# working.net
KiCad netlist of a schematic drawn in EAGLE
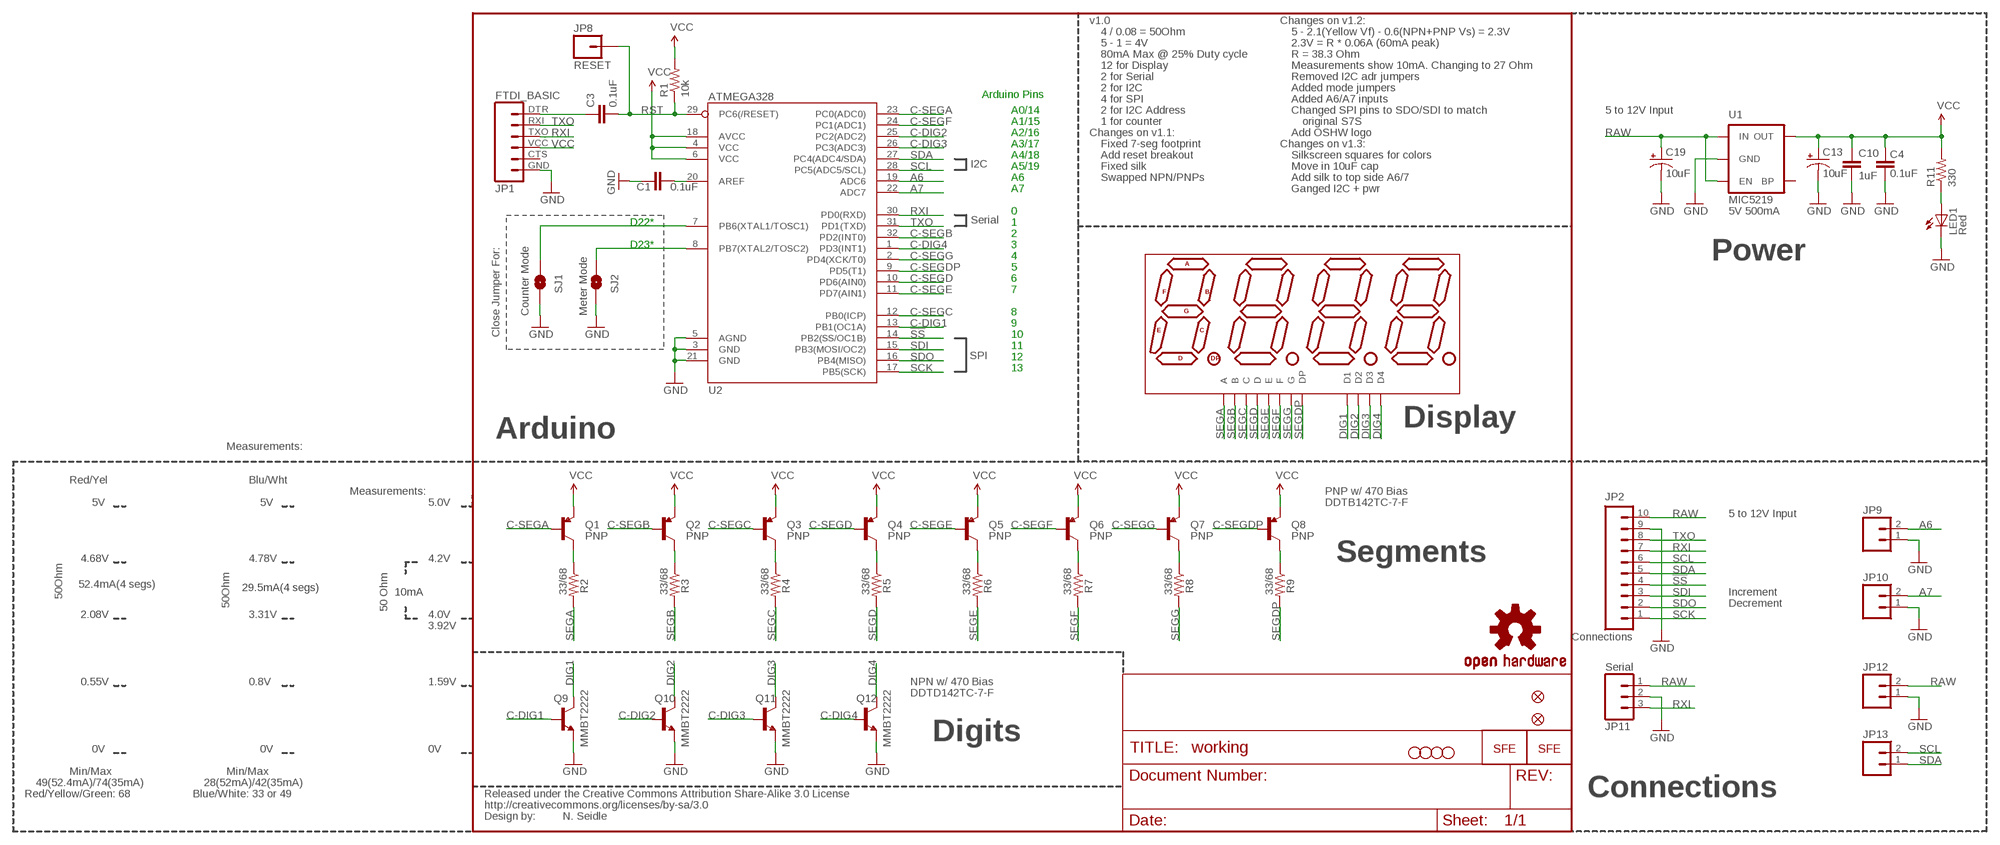
[diagram p0: schematic, sheet 1]

(export (version "E")
  (design (tool "Eeschema 10.0.6"))
  (components
    (comp (ref "C1")
      (value "0.1uF")
      (footprint "eagle-import:0402-CAP")
      (libsource (lib "eagle-import") (part "CAP0402-CAP"))
    )
    (comp (ref "C3")
      (value "0.1uF")
      (footprint "eagle-import:0402-CAP")
      (libsource (lib "eagle-import") (part "CAP0402-CAP"))
    )
    (comp (ref "C4")
      (value "0.1uF")
      (footprint "eagle-import:0402-CAP")
      (libsource (lib "eagle-import") (part "CAP0402-CAP"))
    )
    (comp (ref "C10")
      (value "1uF")
      (footprint "eagle-import:0402-CAP")
      (libsource (lib "eagle-import") (part "CAP0402-CAP"))
    )
    (comp (ref "C13")
      (value "10uF")
      (footprint "eagle-import:EIA3216")
      (libsource (lib "eagle-import") (part "CAP_POL1206"))
    )
    (comp (ref "C19")
      (value "10uF")
      (footprint "eagle-import:EIA3216")
      (libsource (lib "eagle-import") (part "CAP_POL1206"))
    )
    (comp (ref "JP1")
      (value "FTDI_BASIC")
      (footprint "eagle-import:FTDI_BASIC")
      (libsource (lib "eagle-import") (part "FTDI_BASICPTH"))
    )
    (comp (ref "JP2")
      (value "Connections")
      (footprint "eagle-import:1X10")
      (libsource (lib "eagle-import") (part "M10{dblquote}"))
    )
    (comp (ref "JP3")
      (value "STAND-OFF")
      (footprint "eagle-import:STAND-OFF")
      (libsource (lib "eagle-import") (part "STAND-OFF"))
    )
    (comp (ref "JP4")
      (value "STAND-OFF")
      (footprint "eagle-import:STAND-OFF")
      (libsource (lib "eagle-import") (part "STAND-OFF"))
    )
    (comp (ref "JP5")
      (value "STAND-OFF")
      (footprint "eagle-import:STAND-OFF")
      (libsource (lib "eagle-import") (part "STAND-OFF"))
    )
    (comp (ref "JP6")
      (value "STAND-OFF")
      (footprint "eagle-import:STAND-OFF")
      (libsource (lib "eagle-import") (part "STAND-OFF"))
    )
    (comp (ref "JP7")
      (value "FIDUCIALUFIDUCIAL")
      (footprint "eagle-import:MICRO-FIDUCIAL")
      (libsource (lib "eagle-import") (part "FIDUCIALUFIDUCIAL"))
    )
    (comp (ref "JP8")
      (value "RESET")
      (footprint "eagle-import:1X01")
      (libsource (lib "eagle-import") (part "M01PTH"))
    )
    (comp (ref "JP9")
      (value "M02PTH")
      (footprint "eagle-import:1X02")
      (libsource (lib "eagle-import") (part "M02PTH"))
    )
    (comp (ref "JP10")
      (value "M02PTH")
      (footprint "eagle-import:1X02")
      (libsource (lib "eagle-import") (part "M02PTH"))
    )
    (comp (ref "JP11")
      (value "Serial")
      (footprint "eagle-import:JST-3-PTH")
      (libsource (lib "eagle-import") (part "M03JST-PTH"))
    )
    (comp (ref "JP12")
      (value "M02PTH")
      (footprint "eagle-import:1X02")
      (libsource (lib "eagle-import") (part "M02PTH"))
    )
    (comp (ref "JP13")
      (value "M02PTH")
      (footprint "eagle-import:1X02")
      (libsource (lib "eagle-import") (part "M02PTH"))
    )
    (comp (ref "JP14")
      (value "FIDUCIALUFIDUCIAL")
      (footprint "eagle-import:MICRO-FIDUCIAL")
      (libsource (lib "eagle-import") (part "FIDUCIALUFIDUCIAL"))
    )
    (comp (ref "LED1")
      (value "Red")
      (footprint "eagle-import:LED-0603")
      (libsource (lib "eagle-import") (part "LED0603"))
    )
    (comp (ref "Q1")
      (value "PNP")
      (footprint "eagle-import:SOT23-3")
      (libsource (lib "eagle-import") (part "TRANSISTOR_PNPSMD"))
    )
    (comp (ref "Q2")
      (value "PNP")
      (footprint "eagle-import:SOT23-3")
      (libsource (lib "eagle-import") (part "TRANSISTOR_PNPSMD"))
    )
    (comp (ref "Q3")
      (value "PNP")
      (footprint "eagle-import:SOT23-3")
      (libsource (lib "eagle-import") (part "TRANSISTOR_PNPSMD"))
    )
    (comp (ref "Q4")
      (value "PNP")
      (footprint "eagle-import:SOT23-3")
      (libsource (lib "eagle-import") (part "TRANSISTOR_PNPSMD"))
    )
    (comp (ref "Q5")
      (value "PNP")
      (footprint "eagle-import:SOT23-3")
      (libsource (lib "eagle-import") (part "TRANSISTOR_PNPSMD"))
    )
    (comp (ref "Q6")
      (value "PNP")
      (footprint "eagle-import:SOT23-3")
      (libsource (lib "eagle-import") (part "TRANSISTOR_PNPSMD"))
    )
    (comp (ref "Q7")
      (value "PNP")
      (footprint "eagle-import:SOT23-3")
      (libsource (lib "eagle-import") (part "TRANSISTOR_PNPSMD"))
    )
    (comp (ref "Q8")
      (value "PNP")
      (footprint "eagle-import:SOT23-3")
      (libsource (lib "eagle-import") (part "TRANSISTOR_PNPSMD"))
    )
    (comp (ref "Q9")
      (value "MMBT2222")
      (footprint "eagle-import:SOT23-3")
      (libsource (lib "eagle-import") (part "TRANSISTOR_NPNSOT23-3"))
    )
    (comp (ref "Q10")
      (value "MMBT2222")
      (footprint "eagle-import:SOT23-3")
      (libsource (lib "eagle-import") (part "TRANSISTOR_NPNSOT23-3"))
    )
    (comp (ref "Q11")
      (value "MMBT2222")
      (footprint "eagle-import:SOT23-3")
      (libsource (lib "eagle-import") (part "TRANSISTOR_NPNSOT23-3"))
    )
    (comp (ref "Q12")
      (value "MMBT2222")
      (footprint "eagle-import:SOT23-3")
      (libsource (lib "eagle-import") (part "TRANSISTOR_NPNSOT23-3"))
    )
    (comp (ref "R1")
      (value "10k")
      (footprint "eagle-import:0402-RES")
      (libsource (lib "eagle-import") (part "RESISTOR0402-RES"))
    )
    (comp (ref "R2")
      (value "33/68")
      (footprint "eagle-import:0402-RES")
      (libsource (lib "eagle-import") (part "RESISTOR0402-RES"))
    )
    (comp (ref "R3")
      (value "33/68")
      (footprint "eagle-import:0402-RES")
      (libsource (lib "eagle-import") (part "RESISTOR0402-RES"))
    )
    (comp (ref "R4")
      (value "33/68")
      (footprint "eagle-import:0402-RES")
      (libsource (lib "eagle-import") (part "RESISTOR0402-RES"))
    )
    (comp (ref "R5")
      (value "33/68")
      (footprint "eagle-import:0402-RES")
      (libsource (lib "eagle-import") (part "RESISTOR0402-RES"))
    )
    (comp (ref "R6")
      (value "33/68")
      (footprint "eagle-import:0402-RES")
      (libsource (lib "eagle-import") (part "RESISTOR0402-RES"))
    )
    (comp (ref "R7")
      (value "33/68")
      (footprint "eagle-import:0402-RES")
      (libsource (lib "eagle-import") (part "RESISTOR0402-RES"))
    )
    (comp (ref "R8")
      (value "33/68")
      (footprint "eagle-import:0402-RES")
      (libsource (lib "eagle-import") (part "RESISTOR0402-RES"))
    )
    (comp (ref "R9")
      (value "33/68")
      (footprint "eagle-import:0402-RES")
      (libsource (lib "eagle-import") (part "RESISTOR0402-RES"))
    )
    (comp (ref "R11")
      (value "330")
      (footprint "eagle-import:0402-RES")
      (libsource (lib "eagle-import") (part "RESISTOR0402-RES"))
    )
    (comp (ref "SJ1")
      (value "Counter Ctl")
      (footprint "eagle-import:SJ_2S-NO")
      (libsource (lib "eagle-import") (part "SOLDERJUMPERNO"))
    )
    (comp (ref "SJ2")
      (value "Counter Ctl")
      (footprint "eagle-import:SJ_2S-NO")
      (libsource (lib "eagle-import") (part "SOLDERJUMPERNO"))
    )
    (comp (ref "U$2")
      (value "LOGO-SFESK")
      (footprint "eagle-import:SFE-LOGO-FLAME")
      (libsource (lib "eagle-import") (part "LOGO-SFESK"))
    )
    (comp (ref "U$3")
      (value "CREATIVE_COMMONS")
      (footprint "eagle-import:CREATIVE_COMMONS")
      (libsource (lib "eagle-import") (part "CREATIVE_COMMONS"))
    )
    (comp (ref "U$4")
      (value "OSHW-LOGOS")
      (footprint "eagle-import:OSHW-LOGO-S")
      (libsource (lib "eagle-import") (part "OSHW-LOGOS"))
    )
    (comp (ref "U$7")
      (value "LOGO-SFENW2")
      (footprint "eagle-import:SFE-NEW-WEB")
      (libsource (lib "eagle-import") (part "LOGO-SFENW2"))
    )
    (comp (ref "U1")
      (value "MIC5219")
      (footprint "eagle-import:SOT23-5")
      (libsource (lib "eagle-import") (part "V_REG_LDOSMD"))
    )
    (comp (ref "U2")
      (value "ATMEGA328")
      (footprint "eagle-import:TQFP32-08")
      (libsource (lib "eagle-import") (part "ATMEGA168"))
    )
    (comp (ref "U3")
      (value "7-SEGMENT-4DIGIT-COUNTERPTH")
      (footprint "eagle-import:7-SEGMENT-4DIGIT-COUNTER")
      (libsource (lib "eagle-import") (part "7-SEGMENT-4DIGIT-COUNTERPTH"))
    )
  )
  (nets
    (net (code "1") (name "/A6") (class "Default")
      (node (ref "JP9") (pin "2") (pinfunction "2_2") (pintype "passive"))
      (node (ref "U2") (pin "19") (pinfunction "ADC6_19") (pintype "bidirectional"))
    )
    (net (code "2") (name "/A7") (class "Default")
      (node (ref "JP10") (pin "2") (pinfunction "2_2") (pintype "passive"))
      (node (ref "U2") (pin "22") (pinfunction "ADC7_22") (pintype "bidirectional"))
    )
    (net (code "3") (name "/C-DIG1") (class "Default")
      (node (ref "Q9") (pin "1") (pinfunction "B_1") (pintype "passive"))
      (node (ref "U2") (pin "13") (pinfunction "PB1(OC1A)_13") (pintype "bidirectional"))
    )
    (net (code "4") (name "/C-DIG2") (class "Default")
      (node (ref "Q10") (pin "1") (pinfunction "B_1") (pintype "passive"))
      (node (ref "U2") (pin "25") (pinfunction "PC2(ADC2)_25") (pintype "bidirectional"))
    )
    (net (code "5") (name "/C-DIG3") (class "Default")
      (node (ref "Q11") (pin "1") (pinfunction "B_1") (pintype "passive"))
      (node (ref "U2") (pin "26") (pinfunction "PC3(ADC3)_26") (pintype "bidirectional"))
    )
    (net (code "6") (name "/C-DIG4") (class "Default")
      (node (ref "Q12") (pin "1") (pinfunction "B_1") (pintype "passive"))
      (node (ref "U2") (pin "1") (pinfunction "PD3(INT1)_1") (pintype "bidirectional"))
    )
    (net (code "7") (name "/C-SEGA") (class "Default")
      (node (ref "Q1") (pin "1") (pinfunction "B_1") (pintype "passive"))
      (node (ref "U2") (pin "23") (pinfunction "PC0(ADC0)_23") (pintype "bidirectional"))
    )
    (net (code "8") (name "/C-SEGB") (class "Default")
      (node (ref "Q2") (pin "1") (pinfunction "B_1") (pintype "passive"))
      (node (ref "U2") (pin "32") (pinfunction "PD2(INT0)_32") (pintype "bidirectional"))
    )
    (net (code "9") (name "/C-SEGC") (class "Default")
      (node (ref "Q3") (pin "1") (pinfunction "B_1") (pintype "passive"))
      (node (ref "U2") (pin "12") (pinfunction "PB0(ICP)_12") (pintype "bidirectional"))
    )
    (net (code "10") (name "/C-SEGD") (class "Default")
      (node (ref "Q4") (pin "1") (pinfunction "B_1") (pintype "passive"))
      (node (ref "U2") (pin "10") (pinfunction "PD6(AIN0)_10") (pintype "bidirectional"))
    )
    (net (code "11") (name "/C-SEGDP") (class "Default")
      (node (ref "Q8") (pin "1") (pinfunction "B_1") (pintype "passive"))
      (node (ref "U2") (pin "9") (pinfunction "PD5(T1)_9") (pintype "bidirectional"))
    )
    (net (code "12") (name "/C-SEGE") (class "Default")
      (node (ref "Q5") (pin "1") (pinfunction "B_1") (pintype "passive"))
      (node (ref "U2") (pin "11") (pinfunction "PD7(AIN1)_11") (pintype "bidirectional"))
    )
    (net (code "13") (name "/C-SEGF") (class "Default")
      (node (ref "Q6") (pin "1") (pinfunction "B_1") (pintype "passive"))
      (node (ref "U2") (pin "24") (pinfunction "PC1(ADC1)_24") (pintype "bidirectional"))
    )
    (net (code "14") (name "/C-SEGG") (class "Default")
      (node (ref "Q7") (pin "1") (pinfunction "B_1") (pintype "passive"))
      (node (ref "U2") (pin "2") (pinfunction "PD4(XCK/T0)_2") (pintype "bidirectional"))
    )
    (net (code "15") (name "/DIG1") (class "Default")
      (node (ref "Q9") (pin "3") (pinfunction "C_3") (pintype "passive"))
      (node (ref "U3") (pin "12") (pinfunction "D1_12") (pintype "bidirectional"))
    )
    (net (code "16") (name "/DIG2") (class "Default")
      (node (ref "Q10") (pin "3") (pinfunction "C_3") (pintype "passive"))
      (node (ref "U3") (pin "9") (pinfunction "D2_9") (pintype "bidirectional"))
    )
    (net (code "17") (name "/DIG3") (class "Default")
      (node (ref "Q11") (pin "3") (pinfunction "C_3") (pintype "passive"))
      (node (ref "U3") (pin "8") (pinfunction "D3_8") (pintype "bidirectional"))
    )
    (net (code "18") (name "/DIG4") (class "Default")
      (node (ref "Q12") (pin "3") (pinfunction "C_3") (pintype "passive"))
      (node (ref "U3") (pin "6") (pinfunction "D4_6") (pintype "bidirectional"))
    )
    (net (code "19") (name "/RAW") (class "Default")
      (node (ref "C19") (pin "A") (pinfunction "+_A") (pintype "passive"))
      (node (ref "JP11") (pin "1") (pinfunction "1_1") (pintype "passive"))
      (node (ref "JP12") (pin "2") (pinfunction "2_2") (pintype "passive"))
      (node (ref "JP2") (pin "10") (pinfunction "10_10") (pintype "passive"))
      (node (ref "U1") (pin "1") (pinfunction "IN_1") (pintype "input"))
      (node (ref "U1") (pin "3") (pinfunction "EN_3") (pintype "input"))
    )
    (net (code "20") (name "/RST") (class "Default")
      (node (ref "C3") (pin "2") (pinfunction "2_2") (pintype "passive"))
      (node (ref "JP8") (pin "1") (pinfunction "1_1") (pintype "passive"))
      (node (ref "R1") (pin "1") (pinfunction "1_1") (pintype "passive"))
      (node (ref "U2") (pin "29") (pinfunction "PC6(/RESET)_29") (pintype "bidirectional"))
    )
    (net (code "21") (name "/RXI") (class "Default")
      (node (ref "JP1") (pin "TXO") (pinfunction "3_TXO") (pintype "passive"))
      (node (ref "JP11") (pin "3") (pinfunction "3_3") (pintype "passive"))
      (node (ref "JP2") (pin "7") (pinfunction "7_7") (pintype "passive"))
      (node (ref "U2") (pin "30") (pinfunction "PD0(RXD)_30") (pintype "bidirectional"))
    )
    (net (code "22") (name "/SCK") (class "Default")
      (node (ref "JP2") (pin "1") (pinfunction "1_1") (pintype "passive"))
      (node (ref "U2") (pin "17") (pinfunction "PB5(SCK)_17") (pintype "bidirectional"))
    )
    (net (code "23") (name "/SCL") (class "Default")
      (node (ref "JP13") (pin "2") (pinfunction "2_2") (pintype "passive"))
      (node (ref "JP2") (pin "6") (pinfunction "6_6") (pintype "passive"))
      (node (ref "U2") (pin "28") (pinfunction "PC5(ADC5/SCL)_28") (pintype "bidirectional"))
    )
    (net (code "24") (name "/SDA") (class "Default")
      (node (ref "JP13") (pin "1") (pinfunction "1_1") (pintype "passive"))
      (node (ref "JP2") (pin "5") (pinfunction "5_5") (pintype "passive"))
      (node (ref "U2") (pin "27") (pinfunction "PC4(ADC4/SDA)_27") (pintype "bidirectional"))
    )
    (net (code "25") (name "/SDI") (class "Default")
      (node (ref "JP2") (pin "3") (pinfunction "3_3") (pintype "passive"))
      (node (ref "U2") (pin "15") (pinfunction "PB3(MOSI/OC2)_15") (pintype "bidirectional"))
    )
    (net (code "26") (name "/SDO") (class "Default")
      (node (ref "JP2") (pin "2") (pinfunction "2_2") (pintype "passive"))
      (node (ref "U2") (pin "16") (pinfunction "PB4(MISO)_16") (pintype "bidirectional"))
    )
    (net (code "27") (name "/SEGA") (class "Default")
      (node (ref "R2") (pin "2") (pinfunction "2_2") (pintype "passive"))
      (node (ref "U3") (pin "11") (pinfunction "A_11") (pintype "bidirectional"))
    )
    (net (code "28") (name "/SEGB") (class "Default")
      (node (ref "R3") (pin "2") (pinfunction "2_2") (pintype "passive"))
      (node (ref "U3") (pin "7") (pinfunction "B_7") (pintype "bidirectional"))
    )
    (net (code "29") (name "/SEGC") (class "Default")
      (node (ref "R4") (pin "2") (pinfunction "2_2") (pintype "passive"))
      (node (ref "U3") (pin "4") (pinfunction "C_4") (pintype "bidirectional"))
    )
    (net (code "30") (name "/SEGD") (class "Default")
      (node (ref "R5") (pin "2") (pinfunction "2_2") (pintype "passive"))
      (node (ref "U3") (pin "2") (pinfunction "D_2") (pintype "bidirectional"))
    )
    (net (code "31") (name "/SEGDP") (class "Default")
      (node (ref "R9") (pin "2") (pinfunction "2_2") (pintype "passive"))
      (node (ref "U3") (pin "3") (pinfunction "DP_3") (pintype "bidirectional"))
    )
    (net (code "32") (name "/SEGE") (class "Default")
      (node (ref "R6") (pin "2") (pinfunction "2_2") (pintype "passive"))
      (node (ref "U3") (pin "1") (pinfunction "E_1") (pintype "bidirectional"))
    )
    (net (code "33") (name "/SEGF") (class "Default")
      (node (ref "R7") (pin "2") (pinfunction "2_2") (pintype "passive"))
      (node (ref "U3") (pin "10") (pinfunction "F_10") (pintype "bidirectional"))
    )
    (net (code "34") (name "/SEGG") (class "Default")
      (node (ref "R8") (pin "2") (pinfunction "2_2") (pintype "passive"))
      (node (ref "U3") (pin "5") (pinfunction "G_5") (pintype "bidirectional"))
    )
    (net (code "35") (name "/TXO") (class "Default")
      (node (ref "JP1") (pin "RXI") (pinfunction "2_RXI") (pintype "passive"))
      (node (ref "JP2") (pin "8") (pinfunction "8_8") (pintype "passive"))
      (node (ref "U2") (pin "31") (pinfunction "PD1(TXD)_31") (pintype "bidirectional"))
    )
    (net (code "36") (name "/~{SS}") (class "Default")
      (node (ref "JP2") (pin "4") (pinfunction "4_4") (pintype "passive"))
      (node (ref "U2") (pin "14") (pinfunction "PB2(SS/OC1B)_14") (pintype "bidirectional"))
    )
    (net (code "37") (name "GND") (class "Default")
      (node (ref "C1") (pin "1") (pinfunction "1_1") (pintype "passive"))
      (node (ref "C10") (pin "2") (pinfunction "2_2") (pintype "passive"))
      (node (ref "C13") (pin "C") (pinfunction "-_C") (pintype "passive"))
      (node (ref "C19") (pin "C") (pinfunction "-_C") (pintype "passive"))
      (node (ref "C4") (pin "1") (pinfunction "1_1") (pintype "passive"))
      (node (ref "JP1") (pin "GND") (pinfunction "6_GND") (pintype "passive"))
      (node (ref "JP10") (pin "1") (pinfunction "1_1") (pintype "passive"))
      (node (ref "JP11") (pin "2") (pinfunction "2_2") (pintype "passive"))
      (node (ref "JP12") (pin "1") (pinfunction "1_1") (pintype "passive"))
      (node (ref "JP2") (pin "9") (pinfunction "9_9") (pintype "passive"))
      (node (ref "JP9") (pin "1") (pinfunction "1_1") (pintype "passive"))
      (node (ref "LED1") (pin "C") (pinfunction "C_C") (pintype "passive"))
      (node (ref "Q10") (pin "2") (pinfunction "E_2") (pintype "passive"))
      (node (ref "Q11") (pin "2") (pinfunction "E_2") (pintype "passive"))
      (node (ref "Q12") (pin "2") (pinfunction "E_2") (pintype "passive"))
      (node (ref "Q9") (pin "2") (pinfunction "E_2") (pintype "passive"))
      (node (ref "SJ1") (pin "2") (pinfunction "2_2") (pintype "passive"))
      (node (ref "SJ2") (pin "2") (pinfunction "2_2") (pintype "passive"))
      (node (ref "U1") (pin "2") (pinfunction "GND_2") (pintype "input"))
      (node (ref "U2") (pin "21") (pinfunction "GND_21") (pintype "bidirectional"))
      (node (ref "U2") (pin "3") (pinfunction "GND_3") (pintype "bidirectional"))
      (node (ref "U2") (pin "5") (pinfunction "AGND_5") (pintype "bidirectional"))
    )
    (net (code "38") (name "Net-(JP1-1)") (class "Default")
      (node (ref "C3") (pin "1") (pinfunction "1_1") (pintype "passive"))
      (node (ref "JP1") (pin "DTR") (pinfunction "1_DTR") (pintype "passive"))
    )
    (net (code "39") (name "Net-(LED1-PadA)") (class "Default")
      (node (ref "LED1") (pin "A") (pinfunction "A_A") (pintype "passive"))
      (node (ref "R11") (pin "1") (pinfunction "1_1") (pintype "passive"))
    )
    (net (code "40") (name "Net-(Q1-C)") (class "Default")
      (node (ref "Q1") (pin "3") (pinfunction "C_3") (pintype "passive"))
      (node (ref "R2") (pin "1") (pinfunction "1_1") (pintype "passive"))
    )
    (net (code "41") (name "Net-(Q2-C)") (class "Default")
      (node (ref "Q2") (pin "3") (pinfunction "C_3") (pintype "passive"))
      (node (ref "R3") (pin "1") (pinfunction "1_1") (pintype "passive"))
    )
    (net (code "42") (name "Net-(Q3-C)") (class "Default")
      (node (ref "Q3") (pin "3") (pinfunction "C_3") (pintype "passive"))
      (node (ref "R4") (pin "1") (pinfunction "1_1") (pintype "passive"))
    )
    (net (code "43") (name "Net-(Q4-C)") (class "Default")
      (node (ref "Q4") (pin "3") (pinfunction "C_3") (pintype "passive"))
      (node (ref "R5") (pin "1") (pinfunction "1_1") (pintype "passive"))
    )
    (net (code "44") (name "Net-(Q5-C)") (class "Default")
      (node (ref "Q5") (pin "3") (pinfunction "C_3") (pintype "passive"))
      (node (ref "R6") (pin "1") (pinfunction "1_1") (pintype "passive"))
    )
    (net (code "45") (name "Net-(Q6-C)") (class "Default")
      (node (ref "Q6") (pin "3") (pinfunction "C_3") (pintype "passive"))
      (node (ref "R7") (pin "1") (pinfunction "1_1") (pintype "passive"))
    )
    (net (code "46") (name "Net-(Q7-C)") (class "Default")
      (node (ref "Q7") (pin "3") (pinfunction "C_3") (pintype "passive"))
      (node (ref "R8") (pin "1") (pinfunction "1_1") (pintype "passive"))
    )
    (net (code "47") (name "Net-(Q8-C)") (class "Default")
      (node (ref "Q8") (pin "3") (pinfunction "C_3") (pintype "passive"))
      (node (ref "R9") (pin "1") (pinfunction "1_1") (pintype "passive"))
    )
    (net (code "48") (name "Net-(U2-AREF)") (class "Default")
      (node (ref "C1") (pin "2") (pinfunction "2_2") (pintype "passive"))
      (node (ref "U2") (pin "20") (pinfunction "AREF_20") (pintype "bidirectional"))
    )
    (net (code "49") (name "Net-(U2-PB6(XTAL1{slash}TOSC1))") (class "Default")
      (node (ref "SJ1") (pin "1") (pinfunction "1_1") (pintype "passive"))
      (node (ref "U2") (pin "7") (pinfunction "PB6(XTAL1/TOSC1)_7") (pintype "bidirectional"))
    )
    (net (code "50") (name "Net-(U2-PB7(XTAL2{slash}TOSC2))") (class "Default")
      (node (ref "SJ2") (pin "1") (pinfunction "1_1") (pintype "passive"))
      (node (ref "U2") (pin "8") (pinfunction "PB7(XTAL2/TOSC2)_8") (pintype "bidirectional"))
    )
    (net (code "51") (name "VCC") (class "Default")
      (node (ref "C10") (pin "1") (pinfunction "1_1") (pintype "passive"))
      (node (ref "C13") (pin "A") (pinfunction "+_A") (pintype "passive"))
      (node (ref "C4") (pin "2") (pinfunction "2_2") (pintype "passive"))
      (node (ref "JP1") (pin "VCC") (pinfunction "4_VCC") (pintype "passive"))
      (node (ref "Q1") (pin "2") (pinfunction "E_2") (pintype "passive"))
      (node (ref "Q2") (pin "2") (pinfunction "E_2") (pintype "passive"))
      (node (ref "Q3") (pin "2") (pinfunction "E_2") (pintype "passive"))
      (node (ref "Q4") (pin "2") (pinfunction "E_2") (pintype "passive"))
      (node (ref "Q5") (pin "2") (pinfunction "E_2") (pintype "passive"))
      (node (ref "Q6") (pin "2") (pinfunction "E_2") (pintype "passive"))
      (node (ref "Q7") (pin "2") (pinfunction "E_2") (pintype "passive"))
      (node (ref "Q8") (pin "2") (pinfunction "E_2") (pintype "passive"))
      (node (ref "R1") (pin "2") (pinfunction "2_2") (pintype "passive"))
      (node (ref "R11") (pin "2") (pinfunction "2_2") (pintype "passive"))
      (node (ref "U1") (pin "5") (pinfunction "OUT_5") (pintype "passive"))
      (node (ref "U2") (pin "18") (pinfunction "AVCC_18") (pintype "bidirectional"))
      (node (ref "U2") (pin "4") (pinfunction "VCC_4") (pintype "bidirectional"))
      (node (ref "U2") (pin "6") (pinfunction "VCC_6") (pintype "bidirectional"))
    )
    (net (code "52") (name "unconnected-(JP1-5-PadCTS)") (class "Default")
      (node (ref "JP1") (pin "CTS") (pinfunction "5_CTS") (pintype "passive"))
    )
    (net (code "53") (name "unconnected-(U1-BP-Pad4)") (class "Default")
      (node (ref "U1") (pin "4") (pinfunction "BP_4") (pintype "input"))
    )
  )
)
